# Sensor.net
KiCad netlist of a schematic drawn in Altium Designer
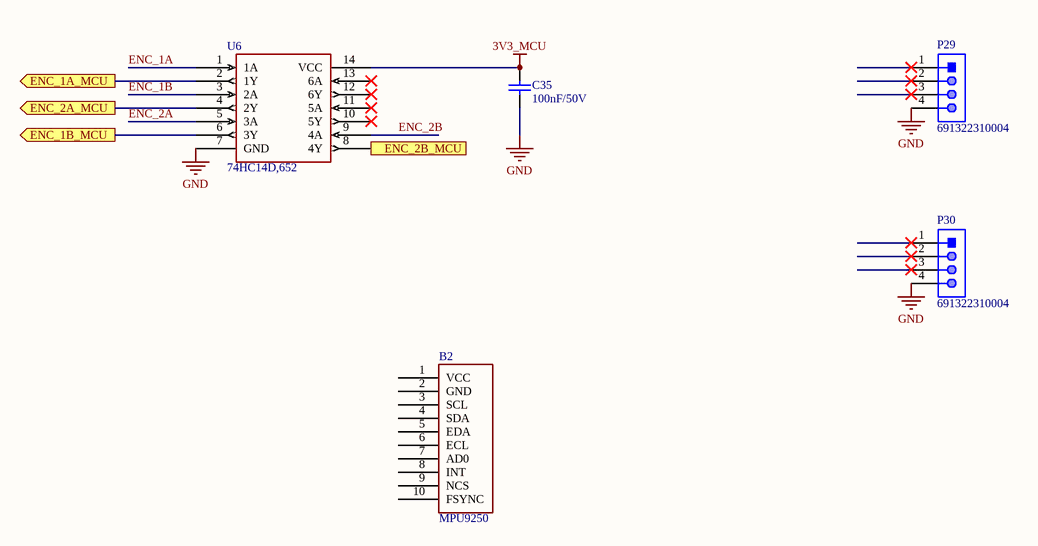
[diagram p0: Sensor.SchDoc]

(export (version "E")
  (design (tool "Eeschema 10.0.6"))
  (components
    (comp (ref "B2") (value "MPU9250") (footprint "MPU9250") (libsource (lib "Board") (part "MPU9250")))
    (comp (ref "C35")
      (value "100nF/50V")
      (footprint "CAP-SM-0805")
      (description "CAP CER 0.1UF 50V Y5V 0805")
      (fields
        (field (name "MANUFACTURER") "Samsung Electro-Mechanics")
        (field (name "MANUFACTURER PART NUMBER") "CL21F104ZBCNNNC")
      )
      (libsource (lib "Capacitor") (part "Cap-100nF-50V-0805"))
    )
    (comp (ref "P29")
      (value "691322310004")
      (footprint "691322310004")
      (description "WR-TBL Serie 322 Horizontal PCB Header, Pluggable, pitch 3.81mm, 4p")
      (fields (field (name "PUBLISHER") "Wurth Elektronik"))
      (libsource (lib "691322310002_Altium_WR-TBL_rev19a") (part "691322310004"))
    )
    (comp (ref "P30")
      (value "691322310004")
      (footprint "691322310004")
      (description "WR-TBL Serie 322 Horizontal PCB Header, Pluggable, pitch 3.81mm, 4p")
      (fields (field (name "PUBLISHER") "Wurth Elektronik"))
      (libsource (lib "691322310002_Altium_WR-TBL_rev19a") (part "691322310004"))
    )
    (comp (ref "U6")
      (value "74HC14D,652")
      (footprint "SOT108-1_NEX")
      (libsource (lib "PIF_robot") (part "74HC14D,652"))
    )
  )
  (nets
    (net (code "1") (name "/ENC_1A") (class "Default")
      (node (ref "U6") (pin "1") (pinfunction "1A_1") (pintype "input"))
    )
    (net (code "2") (name "/ENC_1A_MCU") (class "Default")
      (node (ref "U6") (pin "2") (pinfunction "1Y_2") (pintype "output"))
    )
    (net (code "3") (name "/ENC_1B") (class "Default")
      (node (ref "U6") (pin "3") (pinfunction "2A_3") (pintype "input"))
    )
    (net (code "4") (name "/ENC_1B_MCU") (class "Default")
      (node (ref "U6") (pin "6") (pinfunction "3Y_6") (pintype "output"))
    )
    (net (code "5") (name "/ENC_2A") (class "Default")
      (node (ref "U6") (pin "5") (pinfunction "3A_5") (pintype "input"))
    )
    (net (code "6") (name "/ENC_2A_MCU") (class "Default")
      (node (ref "U6") (pin "4") (pinfunction "2Y_4") (pintype "output"))
    )
    (net (code "7") (name "/ENC_2B") (class "Default")
      (node (ref "U6") (pin "9") (pinfunction "4A_9") (pintype "input"))
    )
    (net (code "8") (name "/ENC_2B_MCU") (class "Default")
      (node (ref "U6") (pin "8") (pinfunction "4Y_8") (pintype "output"))
    )
    (net (code "9") (name "3V3_MCU") (class "Default")
      (node (ref "C35") (pin "2") (pinfunction "2_2") (pintype "passive"))
      (node (ref "U6") (pin "14") (pinfunction "VCC_14") (pintype "power_in"))
    )
    (net (code "10") (name "GND") (class "Default")
      (node (ref "C35") (pin "1") (pinfunction "1_1") (pintype "passive"))
      (node (ref "P29") (pin "4") (pinfunction "4_4") (pintype "passive"))
      (node (ref "P30") (pin "4") (pinfunction "4_4") (pintype "passive"))
      (node (ref "U6") (pin "7") (pinfunction "GND_7") (pintype "power_in"))
    )
    (net (code "11") (name "unconnected-(B2-AD0-Pad7)") (class "Default")
      (node (ref "B2") (pin "7") (pinfunction "AD0_7") (pintype "passive"))
    )
    (net (code "12") (name "unconnected-(B2-ECL-Pad6)") (class "Default")
      (node (ref "B2") (pin "6") (pinfunction "ECL_6") (pintype "passive"))
    )
    (net (code "13") (name "unconnected-(B2-EDA-Pad5)") (class "Default")
      (node (ref "B2") (pin "5") (pinfunction "EDA_5") (pintype "passive"))
    )
    (net (code "14") (name "unconnected-(B2-FSYNC-Pad10)") (class "Default")
      (node (ref "B2") (pin "10") (pinfunction "FSYNC_10") (pintype "passive"))
    )
    (net (code "15") (name "unconnected-(B2-GND-Pad2)") (class "Default")
      (node (ref "B2") (pin "2") (pinfunction "GND_2") (pintype "passive"))
    )
    (net (code "16") (name "unconnected-(B2-INT-Pad8)") (class "Default")
      (node (ref "B2") (pin "8") (pinfunction "INT_8") (pintype "passive"))
    )
    (net (code "17") (name "unconnected-(B2-NCS-Pad9)") (class "Default")
      (node (ref "B2") (pin "9") (pinfunction "NCS_9") (pintype "passive"))
    )
    (net (code "18") (name "unconnected-(B2-SCL-Pad3)") (class "Default")
      (node (ref "B2") (pin "3") (pinfunction "SCL_3") (pintype "passive"))
    )
    (net (code "19") (name "unconnected-(B2-SDA-Pad4)") (class "Default")
      (node (ref "B2") (pin "4") (pinfunction "SDA_4") (pintype "passive"))
    )
    (net (code "20") (name "unconnected-(B2-VCC-Pad1)") (class "Default")
      (node (ref "B2") (pin "1") (pinfunction "VCC_1") (pintype "passive"))
    )
    (net (code "21") (name "unconnected-(P29-Pad1)") (class "Default")
      (node (ref "P29") (pin "1") (pinfunction "1_1") (pintype "passive+no_connect"))
    )
    (net (code "22") (name "unconnected-(P29-Pad2)") (class "Default")
      (node (ref "P29") (pin "2") (pinfunction "2_2") (pintype "passive+no_connect"))
    )
    (net (code "23") (name "unconnected-(P29-Pad3)") (class "Default")
      (node (ref "P29") (pin "3") (pinfunction "3_3") (pintype "passive+no_connect"))
    )
    (net (code "24") (name "unconnected-(P30-Pad1)") (class "Default")
      (node (ref "P30") (pin "1") (pinfunction "1_1") (pintype "passive+no_connect"))
    )
    (net (code "25") (name "unconnected-(P30-Pad2)") (class "Default")
      (node (ref "P30") (pin "2") (pinfunction "2_2") (pintype "passive+no_connect"))
    )
    (net (code "26") (name "unconnected-(P30-Pad3)") (class "Default")
      (node (ref "P30") (pin "3") (pinfunction "3_3") (pintype "passive+no_connect"))
    )
    (net (code "27") (name "unconnected-(U6-5A-Pad11)") (class "Default")
      (node (ref "U6") (pin "11") (pinfunction "5A_11") (pintype "input+no_connect"))
    )
    (net (code "28") (name "unconnected-(U6-5Y-Pad10)") (class "Default")
      (node (ref "U6") (pin "10") (pinfunction "5Y_10") (pintype "output+no_connect"))
    )
    (net (code "29") (name "unconnected-(U6-6A-Pad13)") (class "Default")
      (node (ref "U6") (pin "13") (pinfunction "6A_13") (pintype "input+no_connect"))
    )
    (net (code "30") (name "unconnected-(U6-6Y-Pad12)") (class "Default")
      (node (ref "U6") (pin "12") (pinfunction "6Y_12") (pintype "output+no_connect"))
    )
  )
)
